# frontamp3210105209.net
KiCad netlist of a schematic drawn in Altium Designer
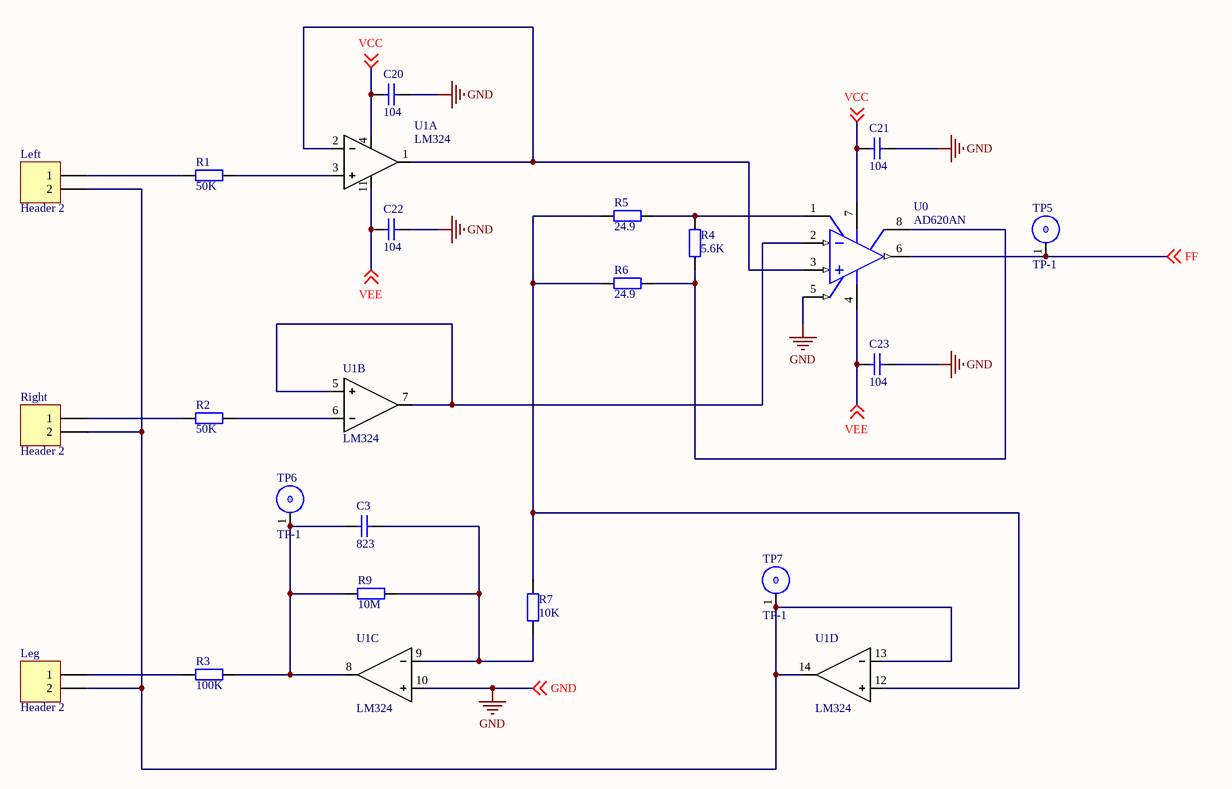
[diagram p0: frontamp3210105209.SchDoc]

(export (version "E")
  (design (tool "Eeschema 10.0.6"))
  (components
    (comp (ref "C3")
      (value "823")
      (footprint "C2")
      (description "Capacitor")
      (fields (field (name "PUBLISHER") "Altium Limited"))
      (libsource (lib "ECG2.0") (part "Cap"))
    )
    (comp (ref "C20")
      (value "104")
      (footprint "C2")
      (description "Capacitor")
      (fields (field (name "PUBLISHER") "Altium Limited"))
      (libsource (lib "ECG2.0") (part "Cap"))
    )
    (comp (ref "C21")
      (value "104")
      (footprint "C2")
      (description "Capacitor")
      (fields (field (name "PUBLISHER") "Altium Limited"))
      (libsource (lib "ECG2.0") (part "Cap"))
    )
    (comp (ref "C22")
      (value "104")
      (footprint "C2")
      (description "Capacitor")
      (fields (field (name "PUBLISHER") "Altium Limited"))
      (libsource (lib "ECG2.0") (part "Cap"))
    )
    (comp (ref "C23")
      (value "104")
      (footprint "C2")
      (description "Capacitor")
      (fields (field (name "PUBLISHER") "Altium Limited"))
      (libsource (lib "ECG2.0") (part "Cap"))
    )
    (comp (ref "Left")
      (value "Header 2")
      (footprint "SIP2L")
      (description "Header, 2-Pin")
      (fields (field (name "PUBLISHER") "Altium Limited"))
      (libsource (lib "ECG2.0") (part "Header 2"))
    )
    (comp (ref "Leg")
      (value "Header 2")
      (footprint "SIP2L")
      (description "Header, 2-Pin")
      (fields (field (name "PUBLISHER") "Altium Limited"))
      (libsource (lib "ECG2.0") (part "Header 2"))
    )
    (comp (ref "R1")
      (value "50K")
      (footprint "AXIAL-0.3")
      (description "Resistor")
      (fields (field (name "PUBLISHER") "Altium Limited"))
      (libsource (lib "ECG2.0") (part "Res2"))
    )
    (comp (ref "R2")
      (value "50K")
      (footprint "AXIAL-0.3")
      (description "Resistor")
      (fields (field (name "PUBLISHER") "Altium Limited"))
      (libsource (lib "ECG2.0") (part "Res2"))
    )
    (comp (ref "R3")
      (value "100K")
      (footprint "AXIAL-0.3")
      (description "Resistor")
      (fields (field (name "PUBLISHER") "Altium Limited"))
      (libsource (lib "ECG2.0") (part "Res2"))
    )
    (comp (ref "R4")
      (value "5.6K")
      (footprint "AXIAL-0.3")
      (description "Resistor")
      (fields (field (name "PUBLISHER") "Altium Limited"))
      (libsource (lib "") (part "Res2_1"))
    )
    (comp (ref "R5")
      (value "24.9")
      (footprint "AXIAL-0.3")
      (description "Resistor")
      (fields (field (name "PUBLISHER") "Altium Limited"))
      (libsource (lib "ECG2.0") (part "Res2"))
    )
    (comp (ref "R6")
      (value "24.9")
      (footprint "AXIAL-0.3")
      (description "Resistor")
      (fields (field (name "PUBLISHER") "Altium Limited"))
      (libsource (lib "ECG2.0") (part "Res2"))
    )
    (comp (ref "R7")
      (value "10K")
      (footprint "AXIAL-0.3")
      (description "Resistor")
      (fields (field (name "PUBLISHER") "Altium Limited"))
      (libsource (lib "") (part "Res2_1"))
    )
    (comp (ref "R9")
      (value "10M")
      (footprint "AXIAL-0.3")
      (description "Resistor")
      (fields (field (name "PUBLISHER") "Altium Limited"))
      (libsource (lib "ECG2.0") (part "Res2"))
    )
    (comp (ref "Right")
      (value "Header 2")
      (footprint "SIP2L")
      (description "Header, 2-Pin")
      (fields (field (name "PUBLISHER") "Altium Limited"))
      (libsource (lib "ECG2.0") (part "Header 2"))
    )
    (comp (ref "TP5") (value "TP-1") (footprint "tp-1-1") (libsource (lib "ECG2.0") (part "TP-1")))
    (comp (ref "TP6") (value "TP-1") (footprint "tp-1-1") (libsource (lib "ECG2.0") (part "TP-1")))
    (comp (ref "TP7") (value "TP-1") (footprint "tp-1-1") (libsource (lib "ECG2.0") (part "TP-1")))
    (comp (ref "U0")
      (value "AD620AN")
      (footprint "DIP8")
      (description "Low-Cost, Low-Power Instrumentation Amplifier")
      (fields (field (name "PUBLISHER") "Altium Limited"))
      (libsource (lib "ECG2.0") (part "AD620AN"))
    )
    (comp (ref "U1") (value "LM324") (footprint "DIP14") (libsource (lib "ECG2.0") (part "LM324")))
  )
  (nets
    (net (code "1") (name "FF") (class "Default")
      (node (ref "TP5") (pin "1") (pintype "passive"))
      (node (ref "U0") (pin "6") (pinfunction "OUT_6") (pintype "output"))
    )
    (net (code "2") (name "GND") (class "Default")
      (node (ref "C20") (pin "2") (pinfunction "2_2") (pintype "passive"))
      (node (ref "C21") (pin "2") (pinfunction "2_2") (pintype "passive"))
      (node (ref "C22") (pin "2") (pinfunction "2_2") (pintype "passive"))
      (node (ref "C23") (pin "2") (pinfunction "2_2") (pintype "passive"))
      (node (ref "U0") (pin "5") (pinfunction "REF_5") (pintype "input"))
      (node (ref "U1") (pin "10") (pinfunction "10_10") (pintype "passive"))
    )
    (net (code "3") (name "Net-(C3-Pad1)") (class "Default")
      (node (ref "C3") (pin "1") (pinfunction "1_1") (pintype "passive"))
      (node (ref "R3") (pin "2") (pinfunction "2_2") (pintype "passive"))
      (node (ref "R9") (pin "1") (pinfunction "1_1") (pintype "passive"))
      (node (ref "TP6") (pin "1") (pintype "passive"))
      (node (ref "U1") (pin "8") (pinfunction "8_8") (pintype "passive"))
    )
    (net (code "4") (name "Net-(C3-Pad2)") (class "Default")
      (node (ref "C3") (pin "2") (pinfunction "2_2") (pintype "passive"))
      (node (ref "R7") (pin "1") (pinfunction "1_1") (pintype "passive"))
      (node (ref "R9") (pin "2") (pinfunction "2_2") (pintype "passive"))
      (node (ref "U1") (pin "9") (pinfunction "9_9") (pintype "passive"))
    )
    (net (code "5") (name "Net-(Left-Pad1)") (class "Default")
      (node (ref "Left") (pin "1") (pinfunction "1_1") (pintype "passive"))
      (node (ref "R1") (pin "1") (pinfunction "1_1") (pintype "passive"))
    )
    (net (code "6") (name "Net-(Left-Pad2)") (class "Default")
      (node (ref "Left") (pin "2") (pinfunction "2_2") (pintype "passive"))
      (node (ref "Leg") (pin "2") (pinfunction "2_2") (pintype "passive"))
      (node (ref "Right") (pin "2") (pinfunction "2_2") (pintype "passive"))
      (node (ref "TP7") (pin "1") (pintype "passive"))
      (node (ref "U1") (pin "13") (pinfunction "13_13") (pintype "passive"))
      (node (ref "U1") (pin "14") (pinfunction "14_14") (pintype "passive"))
    )
    (net (code "7") (name "Net-(Leg-Pad1)") (class "Default")
      (node (ref "Leg") (pin "1") (pinfunction "1_1") (pintype "passive"))
      (node (ref "R3") (pin "1") (pinfunction "1_1") (pintype "passive"))
    )
    (net (code "8") (name "Net-(R1-Pad2)") (class "Default")
      (node (ref "R1") (pin "2") (pinfunction "2_2") (pintype "passive"))
      (node (ref "U1") (pin "3") (pinfunction "3_3") (pintype "passive"))
    )
    (net (code "9") (name "Net-(R2-Pad1)") (class "Default")
      (node (ref "R2") (pin "1") (pinfunction "1_1") (pintype "passive"))
      (node (ref "Right") (pin "1") (pinfunction "1_1") (pintype "passive"))
    )
    (net (code "10") (name "Net-(R2-Pad2)") (class "Default")
      (node (ref "R2") (pin "2") (pinfunction "2_2") (pintype "passive"))
      (node (ref "U1") (pin "6") (pinfunction "6_6") (pintype "passive"))
    )
    (net (code "11") (name "Net-(R4-Pad1)") (class "Default")
      (node (ref "R4") (pin "1") (pinfunction "1_1") (pintype "passive"))
      (node (ref "R6") (pin "2") (pinfunction "2_2") (pintype "passive"))
      (node (ref "U0") (pin "8") (pinfunction "RG_8") (pintype "passive"))
    )
    (net (code "12") (name "Net-(R4-Pad2)") (class "Default")
      (node (ref "R4") (pin "2") (pinfunction "2_2") (pintype "passive"))
      (node (ref "R5") (pin "2") (pinfunction "2_2") (pintype "passive"))
      (node (ref "U0") (pin "1") (pinfunction "RG_1") (pintype "passive"))
    )
    (net (code "13") (name "Net-(R5-Pad1)") (class "Default")
      (node (ref "R5") (pin "1") (pinfunction "1_1") (pintype "passive"))
      (node (ref "R6") (pin "1") (pinfunction "1_1") (pintype "passive"))
      (node (ref "R7") (pin "2") (pinfunction "2_2") (pintype "passive"))
      (node (ref "U1") (pin "12") (pinfunction "12_12") (pintype "passive"))
    )
    (net (code "14") (name "Net-(U0-+IN)") (class "Default")
      (node (ref "U0") (pin "3") (pinfunction "+IN_3") (pintype "input"))
      (node (ref "U1") (pin "1") (pinfunction "1_1") (pintype "passive"))
      (node (ref "U1") (pin "2") (pinfunction "2_2") (pintype "passive"))
    )
    (net (code "15") (name "Net-(U0--IN)") (class "Default")
      (node (ref "U0") (pin "2") (pinfunction "-IN_2") (pintype "input"))
      (node (ref "U1") (pin "5") (pinfunction "5_5") (pintype "passive"))
      (node (ref "U1") (pin "7") (pinfunction "7_7") (pintype "passive"))
    )
    (net (code "16") (name "VCC") (class "Default")
      (node (ref "C20") (pin "1") (pinfunction "1_1") (pintype "passive"))
      (node (ref "C21") (pin "1") (pinfunction "1_1") (pintype "passive"))
      (node (ref "U0") (pin "7") (pinfunction "V+_7") (pintype "power_in"))
      (node (ref "U1") (pin "4") (pinfunction "4_4") (pintype "passive"))
    )
    (net (code "17") (name "VEE") (class "Default")
      (node (ref "C22") (pin "1") (pinfunction "1_1") (pintype "passive"))
      (node (ref "C23") (pin "1") (pinfunction "1_1") (pintype "passive"))
      (node (ref "U0") (pin "4") (pinfunction "V-_4") (pintype "power_in"))
      (node (ref "U1") (pin "11") (pinfunction "11_11") (pintype "passive"))
    )
  )
)
